# MP3.net
KiCad netlist of a schematic drawn in Altium Designer
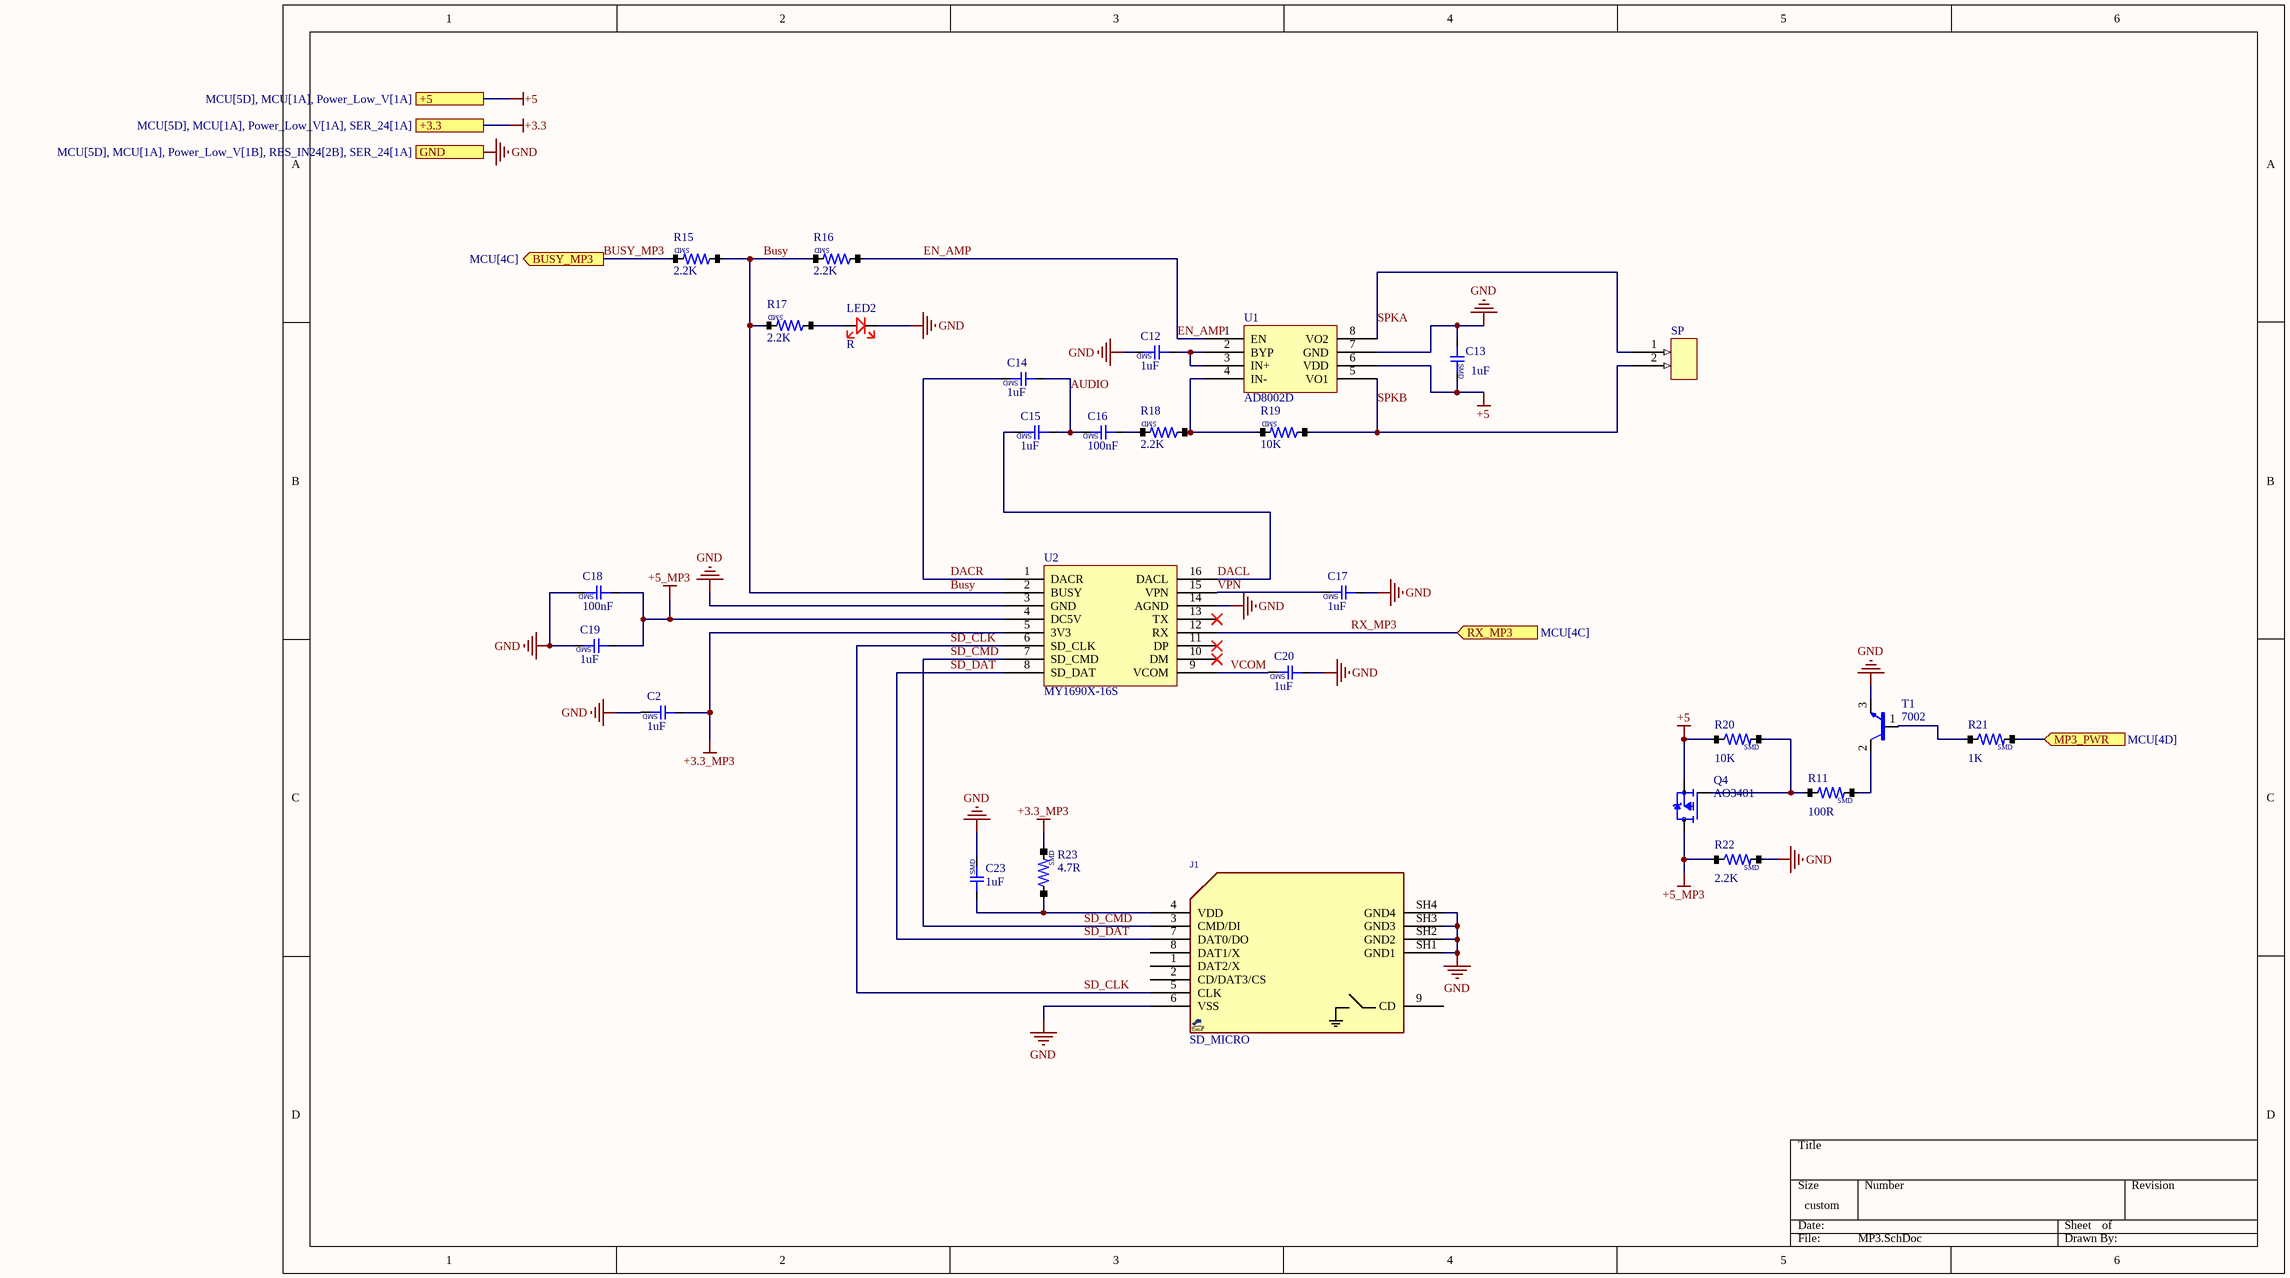
[diagram p0: MP3.SchDoc]

(export (version "E")
  (design (tool "Eeschema 10.0.6"))
  (components
    (comp (ref "C2") (value "1uF") (footprint "CAP-0805") (libsource (lib "kave-eng-pro") (part "cap_smd")))
    (comp (ref "C12") (value "1uF") (footprint "CAP-0805") (libsource (lib "kave-eng-pro") (part "cap_smd")))
    (comp (ref "C13") (value "1uF") (footprint "CAP-0805") (libsource (lib "kave-eng-pro") (part "cap_smd")))
    (comp (ref "C14") (value "1uF") (footprint "CAP-0603") (libsource (lib "kave-eng-pro") (part "cap_smd")))
    (comp (ref "C15") (value "1uF") (footprint "CAP-0603") (libsource (lib "kave-eng-pro") (part "cap_smd")))
    (comp (ref "C16")
      (value "100nF")
      (footprint "CAP-0603")
      (libsource (lib "kave-eng-pro") (part "cap_smd"))
    )
    (comp (ref "C17") (value "1uF") (footprint "CAP-0805") (libsource (lib "kave-eng-pro") (part "cap_smd")))
    (comp (ref "C18") (value "100nF") (footprint "CAP-0603") (libsource (lib "") (part "cap_smd_1")))
    (comp (ref "C19") (value "1uF") (footprint "CAP-0805") (libsource (lib "kave-eng-pro") (part "cap_smd")))
    (comp (ref "C20") (value "1uF") (footprint "CAP-0805") (libsource (lib "kave-eng-pro") (part "cap_smd")))
    (comp (ref "C23") (value "1uF") (footprint "CAP-0805") (libsource (lib "kave-eng-pro") (part "cap_smd")))
    (comp (ref "J1")
      (value "SD_MICRO")
      (footprint "MEMORY_RAVIS")
      (description "SD MICRO exist in Iran, Attend 112J-TDAR-R01")
      (fields (field (name "MANF") "Attend") (field (name "MANF_P#") "112J-TDAR-R01"))
      (libsource (lib "Schlib1") (part "SOCKET_SDMICRO_AT"))
    )
    (comp (ref "LED2")
      (value "R")
      (footprint "LED/0805")
      (libsource (lib "kave-eng-pro") (part "LED-1COLER"))
    )
    (comp (ref "Q4")
      (value "AO3401")
      (footprint "AO3401A")
      (libsource (lib "kave-eng-pro") (part "MOSFET_P_CH"))
    )
    (comp (ref "R11") (value "100R") (footprint "RES/0603") (libsource (lib "kave-eng-pro") (part "RES/SMD")))
    (comp (ref "R15") (value "2.2K") (footprint "RES/0603") (libsource (lib "") (part "RES/SMD_1")))
    (comp (ref "R16") (value "2.2K") (footprint "RES/0603") (libsource (lib "") (part "RES/SMD_1")))
    (comp (ref "R17") (value "2.2K") (footprint "RES/0603") (libsource (lib "") (part "RES/SMD_1")))
    (comp (ref "R18") (value "2.2K") (footprint "RES/0603") (libsource (lib "") (part "RES/SMD_1")))
    (comp (ref "R19") (value "10K") (footprint "RES/0603") (libsource (lib "") (part "RES/SMD_1")))
    (comp (ref "R20") (value "10K") (footprint "RES/0603") (libsource (lib "kave-eng-pro") (part "RES/SMD")))
    (comp (ref "R21") (value "1K") (footprint "RES/0603") (libsource (lib "kave-eng-pro") (part "RES/SMD")))
    (comp (ref "R22") (value "2.2K") (footprint "RES/0603") (libsource (lib "kave-eng-pro") (part "RES/SMD")))
    (comp (ref "R23") (value "4.7R") (footprint "RES/0805") (libsource (lib "") (part "RES/SMD_2")))
    (comp (ref "SP")
      (value "CONECTOR/FONIX/2PIN")
      (footprint "CONECTOR/FONIX/2PIN")
      (libsource (lib "kave-eng-pro") (part "CONECTOR/FONIX/2PIN"))
    )
    (comp (ref "T1") (value "7002") (footprint "SOT23") (libsource (lib "kave-eng-pro") (part "NPN")))
    (comp (ref "U1") (value "AD8002D") (footprint "SOP-8") (libsource (lib "Schlib1") (part "AD8002D")))
    (comp (ref "U2")
      (value "MY1690X-16S")
      (footprint "TL494_SMD")
      (description "IC, MP3 Player")
      (libsource (lib "Schlib1") (part "MY1690X-16S"))
    )
  )
  (nets
    (net (code "2") (name "+3.3_MP3") (class "Default")
      (node (ref "C2") (pin "1") (pintype "passive"))
      (node (ref "R23") (pin "2") (pinfunction "2_2") (pintype "passive"))
      (node (ref "U2") (pin "5") (pinfunction "3V3_5") (pintype "passive"))
    )
    (net (code "3") (name "+5") (class "Default")
      (node (ref "C13") (pin "2") (pintype "passive"))
      (node (ref "Q4") (pin "S") (pinfunction "S_S") (pintype "passive"))
      (node (ref "R20") (pin "1") (pinfunction "1_1") (pintype "passive"))
      (node (ref "U1") (pin "6") (pinfunction "VDD_6") (pintype "passive"))
    )
    (net (code "4") (name "+5_MP3") (class "Default")
      (node (ref "C18") (pin "1") (pintype "passive"))
      (node (ref "C19") (pin "1") (pintype "passive"))
      (node (ref "Q4") (pin "D") (pinfunction "D_D") (pintype "passive"))
      (node (ref "R22") (pin "1") (pinfunction "1_1") (pintype "passive"))
      (node (ref "U2") (pin "4") (pinfunction "DC5V_4") (pintype "passive"))
    )
    (net (code "5") (name "/AUDIO") (class "Default")
      (node (ref "C14") (pin "1") (pintype "passive"))
      (node (ref "C15") (pin "1") (pintype "passive"))
      (node (ref "C16") (pin "2") (pintype "passive"))
    )
    (net (code "6") (name "/BUSY_MP3") (class "Default")
      (node (ref "R15") (pin "2") (pinfunction "2_2") (pintype "passive"))
    )
    (net (code "7") (name "/Busy") (class "Default")
      (node (ref "R15") (pin "1") (pinfunction "1_1") (pintype "passive"))
      (node (ref "R16") (pin "2") (pinfunction "2_2") (pintype "passive"))
      (node (ref "R17") (pin "2") (pinfunction "2_2") (pintype "passive"))
      (node (ref "U2") (pin "2") (pinfunction "BUSY_2") (pintype "passive"))
    )
    (net (code "8") (name "/DACL") (class "Default")
      (node (ref "C15") (pin "2") (pintype "passive"))
      (node (ref "U2") (pin "16") (pinfunction "DACL_16") (pintype "passive"))
    )
    (net (code "9") (name "/DACR") (class "Default")
      (node (ref "C14") (pin "2") (pintype "passive"))
      (node (ref "U2") (pin "1") (pinfunction "DACR_1") (pintype "passive"))
    )
    (net (code "10") (name "/EN_AMP") (class "Default")
      (node (ref "R16") (pin "1") (pinfunction "1_1") (pintype "passive"))
      (node (ref "U1") (pin "1") (pinfunction "EN_1") (pintype "passive"))
    )
    (net (code "11") (name "/MP3_PWR") (class "Default")
      (node (ref "R21") (pin "2") (pinfunction "2_2") (pintype "passive"))
    )
    (net (code "12") (name "/RX_MP3") (class "Default")
      (node (ref "U2") (pin "12") (pinfunction "RX_12") (pintype "passive"))
    )
    (net (code "13") (name "/SD_CLK") (class "Default")
      (node (ref "J1") (pin "5") (pinfunction "CLK_5") (pintype "passive"))
      (node (ref "U2") (pin "6") (pinfunction "SD_CLK_6") (pintype "passive"))
    )
    (net (code "14") (name "/SD_CMD") (class "Default")
      (node (ref "J1") (pin "3") (pinfunction "CMD/DI_3") (pintype "passive"))
      (node (ref "U2") (pin "7") (pinfunction "SD_CMD_7") (pintype "passive"))
    )
    (net (code "15") (name "/SD_DAT") (class "Default")
      (node (ref "J1") (pin "7") (pinfunction "DAT0/DO_7") (pintype "passive"))
      (node (ref "U2") (pin "8") (pinfunction "SD_DAT_8") (pintype "passive"))
    )
    (net (code "16") (name "/SPKA") (class "Default")
      (node (ref "SP") (pin "1") (pintype "input"))
      (node (ref "U1") (pin "8") (pinfunction "VO2_8") (pintype "passive"))
    )
    (net (code "17") (name "/SPKB") (class "Default")
      (node (ref "R19") (pin "1") (pinfunction "1_1") (pintype "passive"))
      (node (ref "SP") (pin "2") (pintype "input"))
      (node (ref "U1") (pin "5") (pinfunction "VO1_5") (pintype "passive"))
    )
    (net (code "18") (name "/VCOM") (class "Default")
      (node (ref "C20") (pin "2") (pintype "passive"))
      (node (ref "U2") (pin "9") (pinfunction "VCOM_9") (pintype "passive"))
    )
    (net (code "19") (name "/VPN") (class "Default")
      (node (ref "C17") (pin "2") (pintype "passive"))
      (node (ref "U2") (pin "15") (pinfunction "VPN_15") (pintype "passive"))
    )
    (net (code "20") (name "GND") (class "Default")
      (node (ref "C12") (pin "2") (pintype "passive"))
      (node (ref "C13") (pin "1") (pintype "passive"))
      (node (ref "C17") (pin "1") (pintype "passive"))
      (node (ref "C18") (pin "2") (pintype "passive"))
      (node (ref "C19") (pin "2") (pintype "passive"))
      (node (ref "C2") (pin "2") (pintype "passive"))
      (node (ref "C20") (pin "1") (pintype "passive"))
      (node (ref "C23") (pin "2") (pintype "passive"))
      (node (ref "J1") (pin "6") (pinfunction "VSS_6") (pintype "passive"))
      (node (ref "J1") (pin "SH1") (pinfunction "GND1_SH1") (pintype "passive"))
      (node (ref "J1") (pin "SH2") (pinfunction "GND2_SH2") (pintype "passive"))
      (node (ref "J1") (pin "SH3") (pinfunction "GND3_SH3") (pintype "passive"))
      (node (ref "J1") (pin "SH4") (pinfunction "GND4_SH4") (pintype "passive"))
      (node (ref "LED2") (pin "K") (pintype "passive"))
      (node (ref "R22") (pin "2") (pinfunction "2_2") (pintype "passive"))
      (node (ref "T1") (pin "3") (pinfunction "E_3") (pintype "passive"))
      (node (ref "U1") (pin "7") (pinfunction "GND_7") (pintype "passive"))
      (node (ref "U2") (pin "14") (pinfunction "AGND_14") (pintype "passive"))
      (node (ref "U2") (pin "3") (pinfunction "GND_3") (pintype "passive"))
    )
    (net (code "21") (name "Net-(C16-Pad1)") (class "Default")
      (node (ref "C16") (pin "1") (pintype "passive"))
      (node (ref "R18") (pin "2") (pinfunction "2_2") (pintype "passive"))
    )
    (net (code "22") (name "Net-(J1-VDD)") (class "Default")
      (node (ref "C23") (pin "1") (pintype "passive"))
      (node (ref "J1") (pin "4") (pinfunction "VDD_4") (pintype "passive"))
      (node (ref "R23") (pin "1") (pinfunction "1_1") (pintype "passive"))
    )
    (net (code "23") (name "Net-(LED2-PadA)") (class "Default")
      (node (ref "LED2") (pin "A") (pintype "passive"))
      (node (ref "R17") (pin "1") (pinfunction "1_1") (pintype "passive"))
    )
    (net (code "24") (name "Net-(Q4-PadG)") (class "Default")
      (node (ref "Q4") (pin "G") (pinfunction "G_G") (pintype "passive"))
      (node (ref "R11") (pin "1") (pinfunction "1_1") (pintype "passive"))
      (node (ref "R20") (pin "2") (pinfunction "2_2") (pintype "passive"))
    )
    (net (code "25") (name "Net-(T1-B)") (class "Default")
      (node (ref "R21") (pin "1") (pinfunction "1_1") (pintype "passive"))
      (node (ref "T1") (pin "1") (pinfunction "B_1") (pintype "passive"))
    )
    (net (code "26") (name "Net-(T1-C)") (class "Default")
      (node (ref "R11") (pin "2") (pinfunction "2_2") (pintype "passive"))
      (node (ref "T1") (pin "2") (pinfunction "C_2") (pintype "passive"))
    )
    (net (code "27") (name "Net-(U1-BYP)") (class "Default")
      (node (ref "C12") (pin "1") (pintype "passive"))
      (node (ref "U1") (pin "2") (pinfunction "BYP_2") (pintype "passive"))
      (node (ref "U1") (pin "3") (pinfunction "IN+_3") (pintype "passive"))
    )
    (net (code "28") (name "Net-(U1-IN-)") (class "Default")
      (node (ref "R18") (pin "1") (pinfunction "1_1") (pintype "passive"))
      (node (ref "R19") (pin "2") (pinfunction "2_2") (pintype "passive"))
      (node (ref "U1") (pin "4") (pinfunction "IN-_4") (pintype "passive"))
    )
    (net (code "29") (name "unconnected-(J1-CD-Pad9)") (class "Default")
      (node (ref "J1") (pin "9") (pinfunction "CD_9") (pintype "passive"))
    )
    (net (code "30") (name "unconnected-(J1-CD{slash}DAT3{slash}CS-Pad2)") (class "Default")
      (node (ref "J1") (pin "2") (pinfunction "CD/DAT3/CS_2") (pintype "passive"))
    )
    (net (code "31") (name "unconnected-(J1-DAT1{slash}X-Pad8)") (class "Default")
      (node (ref "J1") (pin "8") (pinfunction "DAT1/X_8") (pintype "passive"))
    )
    (net (code "32") (name "unconnected-(J1-DAT2{slash}X-Pad1)") (class "Default")
      (node (ref "J1") (pin "1") (pinfunction "DAT2/X_1") (pintype "passive"))
    )
    (net (code "33") (name "unconnected-(U2-DM-Pad10)") (class "Default")
      (node (ref "U2") (pin "10") (pinfunction "DM_10") (pintype "passive+no_connect"))
    )
    (net (code "34") (name "unconnected-(U2-DP-Pad11)") (class "Default")
      (node (ref "U2") (pin "11") (pinfunction "DP_11") (pintype "passive+no_connect"))
    )
    (net (code "35") (name "unconnected-(U2-TX-Pad13)") (class "Default")
      (node (ref "U2") (pin "13") (pinfunction "TX_13") (pintype "passive+no_connect"))
    )
  )
)
